# BreadShieldUno.net
KiCad netlist of a schematic drawn in EAGLE
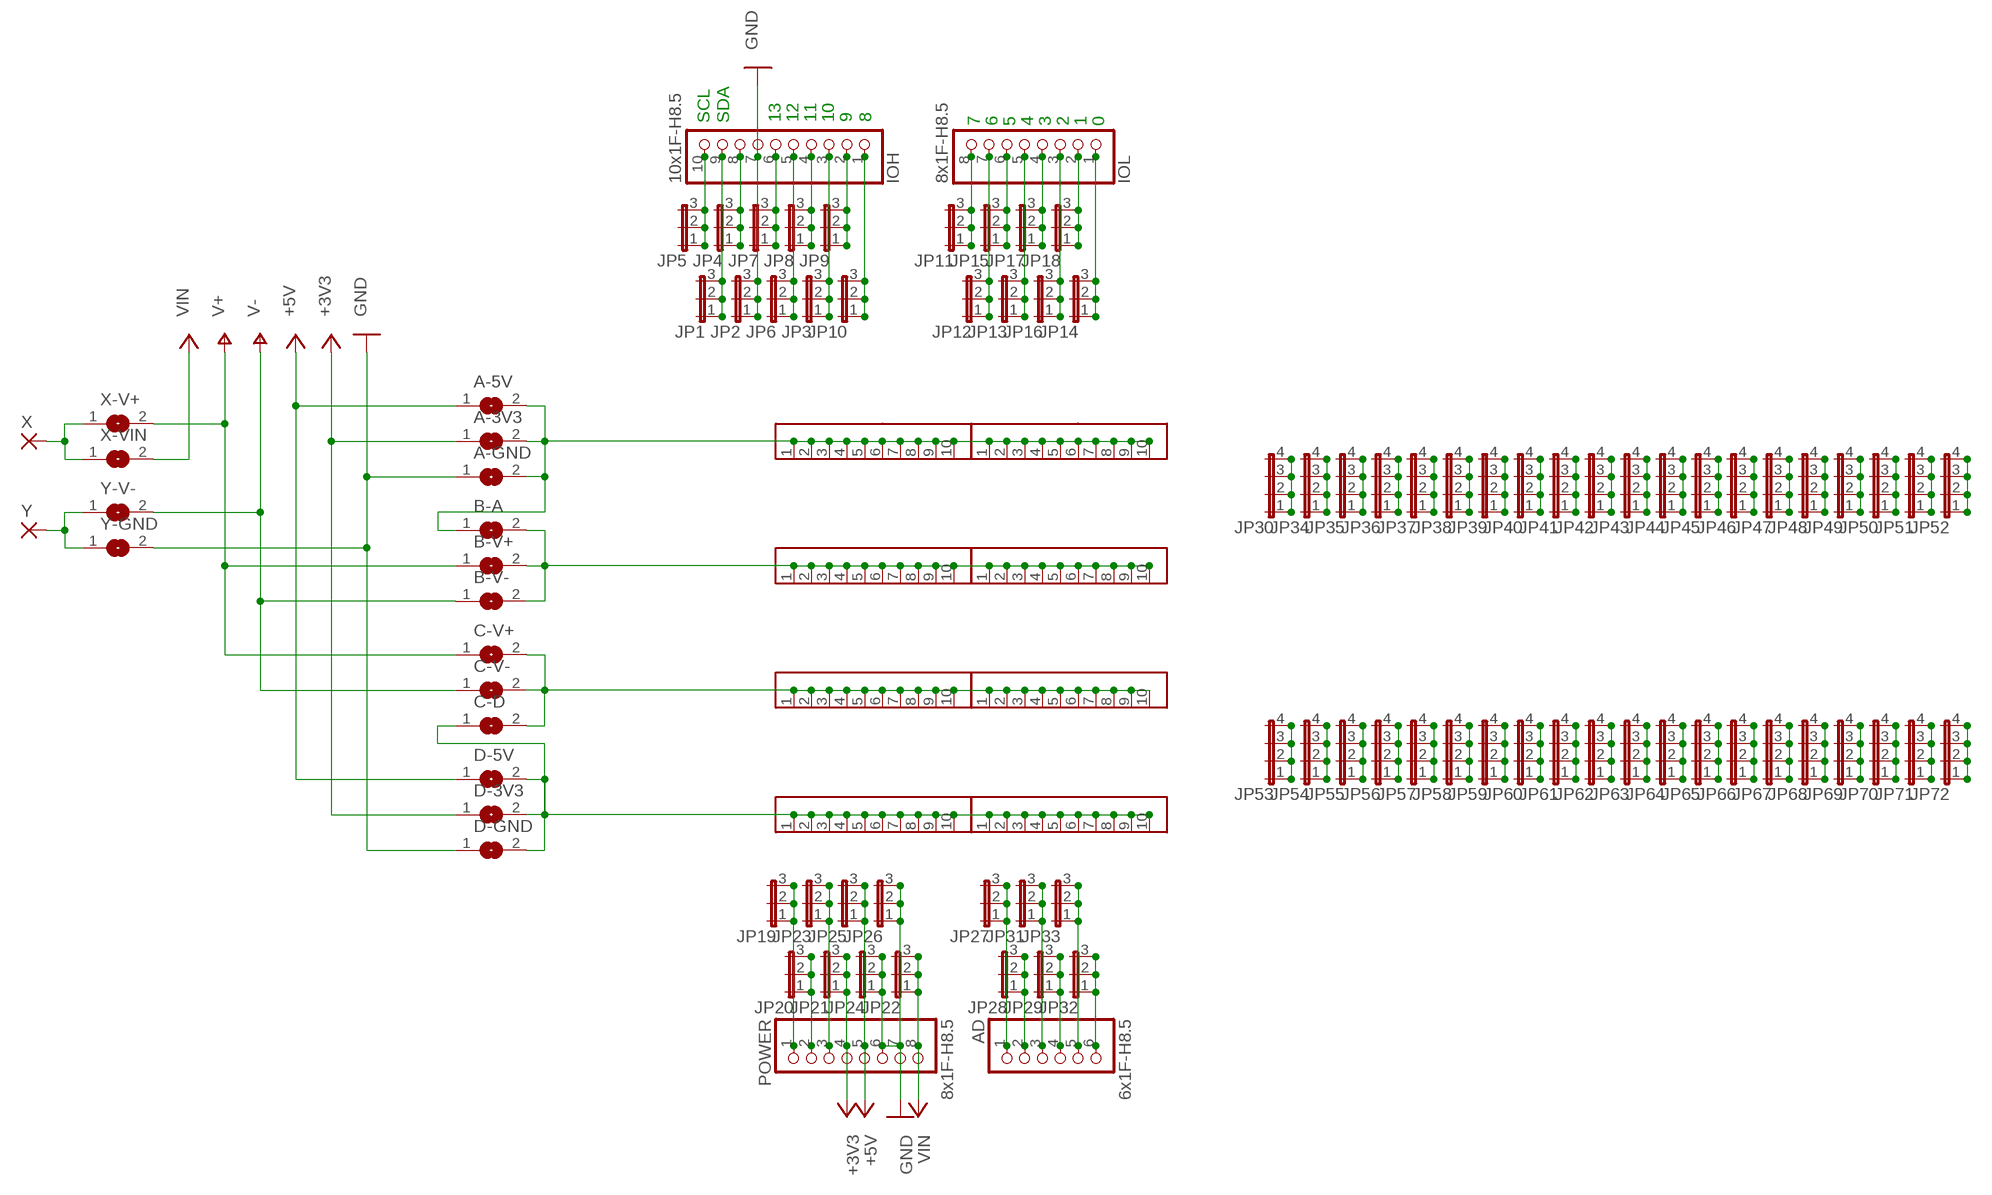
[diagram p0: schematic, sheet 1]

(export (version "E")
  (design (tool "Eeschema 10.0.6"))
  (components
    (comp (ref "A")
      (value "JP10B")
      (footprint "eagle-import:JP10-1")
      (libsource (lib "eagle-import") (part "JP10B"))
    )
    (comp (ref "A-3V3")
      (value "SJ")
      (footprint "eagle-import:SJ")
      (libsource (lib "eagle-import") (part "SJ"))
    )
    (comp (ref "A-5V")
      (value "SJ")
      (footprint "eagle-import:SJ")
      (libsource (lib "eagle-import") (part "SJ"))
    )
    (comp (ref "A-GND")
      (value "SJ")
      (footprint "eagle-import:SJ")
      (libsource (lib "eagle-import") (part "SJ"))
    )
    (comp (ref "A2")
      (value "JP10B")
      (footprint "eagle-import:JP10-1")
      (libsource (lib "eagle-import") (part "JP10B"))
    )
    (comp (ref "AD")
      (value "6x1F-H8.5")
      (footprint "eagle-import:1X06")
      (libsource (lib "eagle-import") (part "PINHD-1X6"))
    )
    (comp (ref "B")
      (value "JP10B")
      (footprint "eagle-import:JP10-1")
      (libsource (lib "eagle-import") (part "JP10B"))
    )
    (comp (ref "B-A") (value "SJ") (footprint "eagle-import:SJ") (libsource (lib "eagle-import") (part "SJ")))
    (comp (ref "B-V+")
      (value "SJ")
      (footprint "eagle-import:SJ")
      (libsource (lib "eagle-import") (part "SJ"))
    )
    (comp (ref "B-V-")
      (value "SJ")
      (footprint "eagle-import:SJ")
      (libsource (lib "eagle-import") (part "SJ"))
    )
    (comp (ref "B2")
      (value "JP10B")
      (footprint "eagle-import:JP10-1")
      (libsource (lib "eagle-import") (part "JP10B"))
    )
    (comp (ref "C")
      (value "JP10B")
      (footprint "eagle-import:JP10-1")
      (libsource (lib "eagle-import") (part "JP10B"))
    )
    (comp (ref "C-D") (value "SJ") (footprint "eagle-import:SJ") (libsource (lib "eagle-import") (part "SJ")))
    (comp (ref "C-V+")
      (value "SJ")
      (footprint "eagle-import:SJ")
      (libsource (lib "eagle-import") (part "SJ"))
    )
    (comp (ref "C-V-")
      (value "SJ")
      (footprint "eagle-import:SJ")
      (libsource (lib "eagle-import") (part "SJ"))
    )
    (comp (ref "C2")
      (value "JP10B")
      (footprint "eagle-import:JP10-1")
      (libsource (lib "eagle-import") (part "JP10B"))
    )
    (comp (ref "D")
      (value "JP10B")
      (footprint "eagle-import:JP10-1")
      (libsource (lib "eagle-import") (part "JP10B"))
    )
    (comp (ref "D-3V3")
      (value "SJ")
      (footprint "eagle-import:SJ")
      (libsource (lib "eagle-import") (part "SJ"))
    )
    (comp (ref "D-5V")
      (value "SJ")
      (footprint "eagle-import:SJ")
      (libsource (lib "eagle-import") (part "SJ"))
    )
    (comp (ref "D-GND")
      (value "SJ")
      (footprint "eagle-import:SJ")
      (libsource (lib "eagle-import") (part "SJ"))
    )
    (comp (ref "D2")
      (value "JP10B")
      (footprint "eagle-import:JP10-1")
      (libsource (lib "eagle-import") (part "JP10B"))
    )
    (comp (ref "IOH")
      (value "10x1F-H8.5")
      (footprint "eagle-import:1X10")
      (libsource (lib "eagle-import") (part "PINHD-1X10_ARD"))
    )
    (comp (ref "IOL")
      (value "8x1F-H8.5")
      (footprint "eagle-import:1X08")
      (libsource (lib "eagle-import") (part "PINHD-1X8"))
    )
    (comp (ref "JP1")
      (value "JP2E")
      (footprint "eagle-import:JP2")
      (libsource (lib "eagle-import") (part "JP2E"))
    )
    (comp (ref "JP2")
      (value "JP2E")
      (footprint "eagle-import:JP2")
      (libsource (lib "eagle-import") (part "JP2E"))
    )
    (comp (ref "JP3")
      (value "JP2E")
      (footprint "eagle-import:JP2")
      (libsource (lib "eagle-import") (part "JP2E"))
    )
    (comp (ref "JP4")
      (value "JP2E")
      (footprint "eagle-import:JP2")
      (libsource (lib "eagle-import") (part "JP2E"))
    )
    (comp (ref "JP5")
      (value "JP2E")
      (footprint "eagle-import:JP2")
      (libsource (lib "eagle-import") (part "JP2E"))
    )
    (comp (ref "JP6")
      (value "JP2E")
      (footprint "eagle-import:JP2")
      (libsource (lib "eagle-import") (part "JP2E"))
    )
    (comp (ref "JP7")
      (value "JP2E")
      (footprint "eagle-import:JP2")
      (libsource (lib "eagle-import") (part "JP2E"))
    )
    (comp (ref "JP8")
      (value "JP2E")
      (footprint "eagle-import:JP2")
      (libsource (lib "eagle-import") (part "JP2E"))
    )
    (comp (ref "JP9")
      (value "JP2E")
      (footprint "eagle-import:JP2")
      (libsource (lib "eagle-import") (part "JP2E"))
    )
    (comp (ref "JP10")
      (value "JP2E")
      (footprint "eagle-import:JP2")
      (libsource (lib "eagle-import") (part "JP2E"))
    )
    (comp (ref "JP11")
      (value "JP2E")
      (footprint "eagle-import:JP2")
      (libsource (lib "eagle-import") (part "JP2E"))
    )
    (comp (ref "JP12")
      (value "JP2E")
      (footprint "eagle-import:JP2")
      (libsource (lib "eagle-import") (part "JP2E"))
    )
    (comp (ref "JP13")
      (value "JP2E")
      (footprint "eagle-import:JP2")
      (libsource (lib "eagle-import") (part "JP2E"))
    )
    (comp (ref "JP14")
      (value "JP2E")
      (footprint "eagle-import:JP2")
      (libsource (lib "eagle-import") (part "JP2E"))
    )
    (comp (ref "JP15")
      (value "JP2E")
      (footprint "eagle-import:JP2")
      (libsource (lib "eagle-import") (part "JP2E"))
    )
    (comp (ref "JP16")
      (value "JP2E")
      (footprint "eagle-import:JP2")
      (libsource (lib "eagle-import") (part "JP2E"))
    )
    (comp (ref "JP17")
      (value "JP2E")
      (footprint "eagle-import:JP2")
      (libsource (lib "eagle-import") (part "JP2E"))
    )
    (comp (ref "JP18")
      (value "JP2E")
      (footprint "eagle-import:JP2")
      (libsource (lib "eagle-import") (part "JP2E"))
    )
    (comp (ref "JP19")
      (value "JP2E")
      (footprint "eagle-import:JP2")
      (libsource (lib "eagle-import") (part "JP2E"))
    )
    (comp (ref "JP20")
      (value "JP2E")
      (footprint "eagle-import:JP2")
      (libsource (lib "eagle-import") (part "JP2E"))
    )
    (comp (ref "JP21")
      (value "JP2E")
      (footprint "eagle-import:JP2")
      (libsource (lib "eagle-import") (part "JP2E"))
    )
    (comp (ref "JP22")
      (value "JP2E")
      (footprint "eagle-import:JP2")
      (libsource (lib "eagle-import") (part "JP2E"))
    )
    (comp (ref "JP23")
      (value "JP2E")
      (footprint "eagle-import:JP2")
      (libsource (lib "eagle-import") (part "JP2E"))
    )
    (comp (ref "JP24")
      (value "JP2E")
      (footprint "eagle-import:JP2")
      (libsource (lib "eagle-import") (part "JP2E"))
    )
    (comp (ref "JP25")
      (value "JP2E")
      (footprint "eagle-import:JP2")
      (libsource (lib "eagle-import") (part "JP2E"))
    )
    (comp (ref "JP26")
      (value "JP2E")
      (footprint "eagle-import:JP2")
      (libsource (lib "eagle-import") (part "JP2E"))
    )
    (comp (ref "JP27")
      (value "JP2E")
      (footprint "eagle-import:JP2")
      (libsource (lib "eagle-import") (part "JP2E"))
    )
    (comp (ref "JP28")
      (value "JP2E")
      (footprint "eagle-import:JP2")
      (libsource (lib "eagle-import") (part "JP2E"))
    )
    (comp (ref "JP29")
      (value "JP2E")
      (footprint "eagle-import:JP2")
      (libsource (lib "eagle-import") (part "JP2E"))
    )
    (comp (ref "JP30")
      (value "JP4E")
      (footprint "eagle-import:JP4")
      (libsource (lib "eagle-import") (part "JP4E"))
    )
    (comp (ref "JP31")
      (value "JP2E")
      (footprint "eagle-import:JP2")
      (libsource (lib "eagle-import") (part "JP2E"))
    )
    (comp (ref "JP32")
      (value "JP2E")
      (footprint "eagle-import:JP2")
      (libsource (lib "eagle-import") (part "JP2E"))
    )
    (comp (ref "JP33")
      (value "JP2E")
      (footprint "eagle-import:JP2")
      (libsource (lib "eagle-import") (part "JP2E"))
    )
    (comp (ref "JP34")
      (value "JP4E")
      (footprint "eagle-import:JP4")
      (libsource (lib "eagle-import") (part "JP4E"))
    )
    (comp (ref "JP35")
      (value "JP4E")
      (footprint "eagle-import:JP4")
      (libsource (lib "eagle-import") (part "JP4E"))
    )
    (comp (ref "JP36")
      (value "JP4E")
      (footprint "eagle-import:JP4")
      (libsource (lib "eagle-import") (part "JP4E"))
    )
    (comp (ref "JP37")
      (value "JP4E")
      (footprint "eagle-import:JP4")
      (libsource (lib "eagle-import") (part "JP4E"))
    )
    (comp (ref "JP38")
      (value "JP4E")
      (footprint "eagle-import:JP4")
      (libsource (lib "eagle-import") (part "JP4E"))
    )
    (comp (ref "JP39")
      (value "JP4E")
      (footprint "eagle-import:JP4")
      (libsource (lib "eagle-import") (part "JP4E"))
    )
    (comp (ref "JP40")
      (value "JP4E")
      (footprint "eagle-import:JP4")
      (libsource (lib "eagle-import") (part "JP4E"))
    )
    (comp (ref "JP41")
      (value "JP4E")
      (footprint "eagle-import:JP4")
      (libsource (lib "eagle-import") (part "JP4E"))
    )
    (comp (ref "JP42")
      (value "JP4E")
      (footprint "eagle-import:JP4")
      (libsource (lib "eagle-import") (part "JP4E"))
    )
    (comp (ref "JP43")
      (value "JP4E")
      (footprint "eagle-import:JP4")
      (libsource (lib "eagle-import") (part "JP4E"))
    )
    (comp (ref "JP44")
      (value "JP4E")
      (footprint "eagle-import:JP4")
      (libsource (lib "eagle-import") (part "JP4E"))
    )
    (comp (ref "JP45")
      (value "JP4E")
      (footprint "eagle-import:JP4")
      (libsource (lib "eagle-import") (part "JP4E"))
    )
    (comp (ref "JP46")
      (value "JP4E")
      (footprint "eagle-import:JP4")
      (libsource (lib "eagle-import") (part "JP4E"))
    )
    (comp (ref "JP47")
      (value "JP4E")
      (footprint "eagle-import:JP4")
      (libsource (lib "eagle-import") (part "JP4E"))
    )
    (comp (ref "JP48")
      (value "JP4E")
      (footprint "eagle-import:JP4")
      (libsource (lib "eagle-import") (part "JP4E"))
    )
    (comp (ref "JP49")
      (value "JP4E")
      (footprint "eagle-import:JP4")
      (libsource (lib "eagle-import") (part "JP4E"))
    )
    (comp (ref "JP50")
      (value "JP4E")
      (footprint "eagle-import:JP4")
      (libsource (lib "eagle-import") (part "JP4E"))
    )
    (comp (ref "JP51")
      (value "JP4E")
      (footprint "eagle-import:JP4")
      (libsource (lib "eagle-import") (part "JP4E"))
    )
    (comp (ref "JP52")
      (value "JP4E")
      (footprint "eagle-import:JP4")
      (libsource (lib "eagle-import") (part "JP4E"))
    )
    (comp (ref "JP53")
      (value "JP4E")
      (footprint "eagle-import:JP4")
      (libsource (lib "eagle-import") (part "JP4E"))
    )
    (comp (ref "JP54")
      (value "JP4E")
      (footprint "eagle-import:JP4")
      (libsource (lib "eagle-import") (part "JP4E"))
    )
    (comp (ref "JP55")
      (value "JP4E")
      (footprint "eagle-import:JP4")
      (libsource (lib "eagle-import") (part "JP4E"))
    )
    (comp (ref "JP56")
      (value "JP4E")
      (footprint "eagle-import:JP4")
      (libsource (lib "eagle-import") (part "JP4E"))
    )
    (comp (ref "JP57")
      (value "JP4E")
      (footprint "eagle-import:JP4")
      (libsource (lib "eagle-import") (part "JP4E"))
    )
    (comp (ref "JP58")
      (value "JP4E")
      (footprint "eagle-import:JP4")
      (libsource (lib "eagle-import") (part "JP4E"))
    )
    (comp (ref "JP59")
      (value "JP4E")
      (footprint "eagle-import:JP4")
      (libsource (lib "eagle-import") (part "JP4E"))
    )
    (comp (ref "JP60")
      (value "JP4E")
      (footprint "eagle-import:JP4")
      (libsource (lib "eagle-import") (part "JP4E"))
    )
    (comp (ref "JP61")
      (value "JP4E")
      (footprint "eagle-import:JP4")
      (libsource (lib "eagle-import") (part "JP4E"))
    )
    (comp (ref "JP62")
      (value "JP4E")
      (footprint "eagle-import:JP4")
      (libsource (lib "eagle-import") (part "JP4E"))
    )
    (comp (ref "JP63")
      (value "JP4E")
      (footprint "eagle-import:JP4")
      (libsource (lib "eagle-import") (part "JP4E"))
    )
    (comp (ref "JP64")
      (value "JP4E")
      (footprint "eagle-import:JP4")
      (libsource (lib "eagle-import") (part "JP4E"))
    )
    (comp (ref "JP65")
      (value "JP4E")
      (footprint "eagle-import:JP4")
      (libsource (lib "eagle-import") (part "JP4E"))
    )
    (comp (ref "JP66")
      (value "JP4E")
      (footprint "eagle-import:JP4")
      (libsource (lib "eagle-import") (part "JP4E"))
    )
    (comp (ref "JP67")
      (value "JP4E")
      (footprint "eagle-import:JP4")
      (libsource (lib "eagle-import") (part "JP4E"))
    )
    (comp (ref "JP68")
      (value "JP4E")
      (footprint "eagle-import:JP4")
      (libsource (lib "eagle-import") (part "JP4E"))
    )
    (comp (ref "JP69")
      (value "JP4E")
      (footprint "eagle-import:JP4")
      (libsource (lib "eagle-import") (part "JP4E"))
    )
    (comp (ref "JP70")
      (value "JP4E")
      (footprint "eagle-import:JP4")
      (libsource (lib "eagle-import") (part "JP4E"))
    )
    (comp (ref "JP71")
      (value "JP4E")
      (footprint "eagle-import:JP4")
      (libsource (lib "eagle-import") (part "JP4E"))
    )
    (comp (ref "JP72")
      (value "JP4E")
      (footprint "eagle-import:JP4")
      (libsource (lib "eagle-import") (part "JP4E"))
    )
    (comp (ref "POWER")
      (value "8x1F-H8.5")
      (footprint "eagle-import:1X08")
      (libsource (lib "eagle-import") (part "PINHD-1X8"))
    )
    (comp (ref "X")
      (value "3,81/1,4")
      (footprint "eagle-import:3,81_1,4")
      (libsource (lib "eagle-import") (part "3,81/1,4"))
    )
    (comp (ref "X-V+")
      (value "SJ")
      (footprint "eagle-import:SJ")
      (libsource (lib "eagle-import") (part "SJ"))
    )
    (comp (ref "X-VIN")
      (value "SJ")
      (footprint "eagle-import:SJ")
      (libsource (lib "eagle-import") (part "SJ"))
    )
    (comp (ref "Y")
      (value "3,81/1,4")
      (footprint "eagle-import:3,81_1,4")
      (libsource (lib "eagle-import") (part "3,81/1,4"))
    )
    (comp (ref "Y-GND")
      (value "SJ")
      (footprint "eagle-import:SJ")
      (libsource (lib "eagle-import") (part "SJ"))
    )
    (comp (ref "Y-V-")
      (value "SJ")
      (footprint "eagle-import:SJ")
      (libsource (lib "eagle-import") (part "SJ"))
    )
  )
  (nets
    (net (code "1") (name "+3V3") (class "Default")
      (node (ref "A-3V3") (pin "1") (pinfunction "1_1") (pintype "passive"))
      (node (ref "D-3V3") (pin "1") (pinfunction "1_1") (pintype "passive"))
      (node (ref "JP21") (pin "1") (pinfunction "1_1") (pintype "passive"))
      (node (ref "JP21") (pin "2") (pinfunction "2_2") (pintype "passive"))
      (node (ref "JP21") (pin "3") (pinfunction "3_3") (pintype "passive"))
      (node (ref "POWER") (pin "4") (pinfunction "4_4") (pintype "passive"))
    )
    (net (code "2") (name "+5V") (class "Default")
      (node (ref "A-5V") (pin "1") (pinfunction "1_1") (pintype "passive"))
      (node (ref "D-5V") (pin "1") (pinfunction "1_1") (pintype "passive"))
      (node (ref "JP25") (pin "1") (pinfunction "1_1") (pintype "passive"))
      (node (ref "JP25") (pin "2") (pinfunction "2_2") (pintype "passive"))
      (node (ref "JP25") (pin "3") (pinfunction "3_3") (pintype "passive"))
      (node (ref "POWER") (pin "5") (pinfunction "5_5") (pintype "passive"))
    )
    (net (code "3") (name "GND") (class "Default")
      (node (ref "A-GND") (pin "1") (pinfunction "1_1") (pintype "passive"))
      (node (ref "D-GND") (pin "1") (pinfunction "1_1") (pintype "passive"))
      (node (ref "IOH") (pin "7") (pinfunction "7_7") (pintype "passive"))
      (node (ref "JP2") (pin "1") (pinfunction "1_1") (pintype "passive"))
      (node (ref "JP2") (pin "2") (pinfunction "2_2") (pintype "passive"))
      (node (ref "JP2") (pin "3") (pinfunction "3_3") (pintype "passive"))
      (node (ref "JP24") (pin "1") (pinfunction "1_1") (pintype "passive"))
      (node (ref "JP24") (pin "2") (pinfunction "2_2") (pintype "passive"))
      (node (ref "JP24") (pin "3") (pinfunction "3_3") (pintype "passive"))
      (node (ref "JP26") (pin "1") (pinfunction "1_1") (pintype "passive"))
      (node (ref "JP26") (pin "2") (pinfunction "2_2") (pintype "passive"))
      (node (ref "JP26") (pin "3") (pinfunction "3_3") (pintype "passive"))
      (node (ref "POWER") (pin "6") (pinfunction "6_6") (pintype "passive"))
      (node (ref "POWER") (pin "7") (pinfunction "7_7") (pintype "passive"))
      (node (ref "Y-GND") (pin "2") (pinfunction "2_2") (pintype "passive"))
    )
    (net (code "4") (name "Net-(A-3V3-Pad2)") (class "Default")
      (node (ref "A") (pin "1") (pinfunction "1_1") (pintype "bidirectional"))
      (node (ref "A") (pin "10") (pinfunction "10_10") (pintype "bidirectional"))
      (node (ref "A") (pin "2") (pinfunction "2_2") (pintype "bidirectional"))
      (node (ref "A") (pin "3") (pinfunction "3_3") (pintype "bidirectional"))
      (node (ref "A") (pin "4") (pinfunction "4_4") (pintype "bidirectional"))
      (node (ref "A") (pin "5") (pinfunction "5_5") (pintype "bidirectional"))
      (node (ref "A") (pin "6") (pinfunction "6_6") (pintype "bidirectional"))
      (node (ref "A") (pin "7") (pinfunction "7_7") (pintype "bidirectional"))
      (node (ref "A") (pin "8") (pinfunction "8_8") (pintype "bidirectional"))
      (node (ref "A") (pin "9") (pinfunction "9_9") (pintype "bidirectional"))
      (node (ref "A-3V3") (pin "2") (pinfunction "2_2") (pintype "passive"))
      (node (ref "A-5V") (pin "2") (pinfunction "2_2") (pintype "passive"))
      (node (ref "A-GND") (pin "2") (pinfunction "2_2") (pintype "passive"))
      (node (ref "A2") (pin "1") (pinfunction "1_1") (pintype "bidirectional"))
      (node (ref "A2") (pin "10") (pinfunction "10_10") (pintype "bidirectional"))
      (node (ref "A2") (pin "2") (pinfunction "2_2") (pintype "bidirectional"))
      (node (ref "A2") (pin "3") (pinfunction "3_3") (pintype "bidirectional"))
      (node (ref "A2") (pin "4") (pinfunction "4_4") (pintype "bidirectional"))
      (node (ref "A2") (pin "5") (pinfunction "5_5") (pintype "bidirectional"))
      (node (ref "A2") (pin "6") (pinfunction "6_6") (pintype "bidirectional"))
      (node (ref "A2") (pin "7") (pinfunction "7_7") (pintype "bidirectional"))
      (node (ref "A2") (pin "8") (pinfunction "8_8") (pintype "bidirectional"))
      (node (ref "A2") (pin "9") (pinfunction "9_9") (pintype "bidirectional"))
      (node (ref "B-A") (pin "1") (pinfunction "1_1") (pintype "passive"))
    )
    (net (code "5") (name "Net-(AD-Pad1)") (class "Default")
      (node (ref "AD") (pin "1") (pinfunction "1_1") (pintype "passive"))
      (node (ref "JP27") (pin "1") (pinfunction "1_1") (pintype "passive"))
      (node (ref "JP27") (pin "2") (pinfunction "2_2") (pintype "passive"))
      (node (ref "JP27") (pin "3") (pinfunction "3_3") (pintype "passive"))
    )
    (net (code "6") (name "Net-(AD-Pad2)") (class "Default")
      (node (ref "AD") (pin "2") (pinfunction "2_2") (pintype "passive"))
      (node (ref "JP28") (pin "1") (pinfunction "1_1") (pintype "passive"))
      (node (ref "JP28") (pin "2") (pinfunction "2_2") (pintype "passive"))
      (node (ref "JP28") (pin "3") (pinfunction "3_3") (pintype "passive"))
    )
    (net (code "7") (name "Net-(AD-Pad3)") (class "Default")
      (node (ref "AD") (pin "3") (pinfunction "3_3") (pintype "passive"))
      (node (ref "JP31") (pin "1") (pinfunction "1_1") (pintype "passive"))
      (node (ref "JP31") (pin "2") (pinfunction "2_2") (pintype "passive"))
      (node (ref "JP31") (pin "3") (pinfunction "3_3") (pintype "passive"))
    )
    (net (code "8") (name "Net-(AD-Pad4)") (class "Default")
      (node (ref "AD") (pin "4") (pinfunction "4_4") (pintype "passive"))
      (node (ref "JP29") (pin "1") (pinfunction "1_1") (pintype "passive"))
      (node (ref "JP29") (pin "2") (pinfunction "2_2") (pintype "passive"))
      (node (ref "JP29") (pin "3") (pinfunction "3_3") (pintype "passive"))
    )
    (net (code "9") (name "Net-(AD-Pad5)") (class "Default")
      (node (ref "AD") (pin "5") (pinfunction "5_5") (pintype "passive"))
      (node (ref "JP33") (pin "1") (pinfunction "1_1") (pintype "passive"))
      (node (ref "JP33") (pin "2") (pinfunction "2_2") (pintype "passive"))
      (node (ref "JP33") (pin "3") (pinfunction "3_3") (pintype "passive"))
    )
    (net (code "10") (name "Net-(AD-Pad6)") (class "Default")
      (node (ref "AD") (pin "6") (pinfunction "6_6") (pintype "passive"))
      (node (ref "JP32") (pin "1") (pinfunction "1_1") (pintype "passive"))
      (node (ref "JP32") (pin "2") (pinfunction "2_2") (pintype "passive"))
      (node (ref "JP32") (pin "3") (pinfunction "3_3") (pintype "passive"))
    )
    (net (code "11") (name "Net-(B-A-Pad2)") (class "Default")
      (node (ref "B") (pin "1") (pinfunction "1_1") (pintype "bidirectional"))
      (node (ref "B") (pin "10") (pinfunction "10_10") (pintype "bidirectional"))
      (node (ref "B") (pin "2") (pinfunction "2_2") (pintype "bidirectional"))
      (node (ref "B") (pin "3") (pinfunction "3_3") (pintype "bidirectional"))
      (node (ref "B") (pin "4") (pinfunction "4_4") (pintype "bidirectional"))
      (node (ref "B") (pin "5") (pinfunction "5_5") (pintype "bidirectional"))
      (node (ref "B") (pin "6") (pinfunction "6_6") (pintype "bidirectional"))
      (node (ref "B") (pin "7") (pinfunction "7_7") (pintype "bidirectional"))
      (node (ref "B") (pin "8") (pinfunction "8_8") (pintype "bidirectional"))
      (node (ref "B") (pin "9") (pinfunction "9_9") (pintype "bidirectional"))
      (node (ref "B-A") (pin "2") (pinfunction "2_2") (pintype "passive"))
      (node (ref "B-V+") (pin "2") (pinfunction "2_2") (pintype "passive"))
      (node (ref "B-V-") (pin "2") (pinfunction "2_2") (pintype "passive"))
      (node (ref "B2") (pin "1") (pinfunction "1_1") (pintype "bidirectional"))
      (node (ref "B2") (pin "10") (pinfunction "10_10") (pintype "bidirectional"))
      (node (ref "B2") (pin "2") (pinfunction "2_2") (pintype "bidirectional"))
      (node (ref "B2") (pin "3") (pinfunction "3_3") (pintype "bidirectional"))
      (node (ref "B2") (pin "4") (pinfunction "4_4") (pintype "bidirectional"))
      (node (ref "B2") (pin "5") (pinfunction "5_5") (pintype "bidirectional"))
      (node (ref "B2") (pin "6") (pinfunction "6_6") (pintype "bidirectional"))
      (node (ref "B2") (pin "7") (pinfunction "7_7") (pintype "bidirectional"))
      (node (ref "B2") (pin "8") (pinfunction "8_8") (pintype "bidirectional"))
      (node (ref "B2") (pin "9") (pinfunction "9_9") (pintype "bidirectional"))
    )
    (net (code "12") (name "Net-(C-D-Pad1)") (class "Default")
      (node (ref "C-D") (pin "1") (pinfunction "1_1") (pintype "passive"))
      (node (ref "D") (pin "1") (pinfunction "1_1") (pintype "bidirectional"))
      (node (ref "D") (pin "10") (pinfunction "10_10") (pintype "bidirectional"))
      (node (ref "D") (pin "2") (pinfunction "2_2") (pintype "bidirectional"))
      (node (ref "D") (pin "3") (pinfunction "3_3") (pintype "bidirectional"))
      (node (ref "D") (pin "4") (pinfunction "4_4") (pintype "bidirectional"))
      (node (ref "D") (pin "5") (pinfunction "5_5") (pintype "bidirectional"))
      (node (ref "D") (pin "6") (pinfunction "6_6") (pintype "bidirectional"))
      (node (ref "D") (pin "7") (pinfunction "7_7") (pintype "bidirectional"))
      (node (ref "D") (pin "8") (pinfunction "8_8") (pintype "bidirectional"))
      (node (ref "D") (pin "9") (pinfunction "9_9") (pintype "bidirectional"))
      (node (ref "D-3V3") (pin "2") (pinfunction "2_2") (pintype "passive"))
      (node (ref "D-5V") (pin "2") (pinfunction "2_2") (pintype "passive"))
      (node (ref "D-GND") (pin "2") (pinfunction "2_2") (pintype "passive"))
      (node (ref "D2") (pin "1") (pinfunction "1_1") (pintype "bidirectional"))
      (node (ref "D2") (pin "10") (pinfunction "10_10") (pintype "bidirectional"))
      (node (ref "D2") (pin "2") (pinfunction "2_2") (pintype "bidirectional"))
      (node (ref "D2") (pin "3") (pinfunction "3_3") (pintype "bidirectional"))
      (node (ref "D2") (pin "4") (pinfunction "4_4") (pintype "bidirectional"))
      (node (ref "D2") (pin "5") (pinfunction "5_5") (pintype "bidirectional"))
      (node (ref "D2") (pin "6") (pinfunction "6_6") (pintype "bidirectional"))
      (node (ref "D2") (pin "7") (pinfunction "7_7") (pintype "bidirectional"))
      (node (ref "D2") (pin "8") (pinfunction "8_8") (pintype "bidirectional"))
      (node (ref "D2") (pin "9") (pinfunction "9_9") (pintype "bidirectional"))
    )
    (net (code "13") (name "Net-(C-D-Pad2)") (class "Default")
      (node (ref "C") (pin "1") (pinfunction "1_1") (pintype "bidirectional"))
      (node (ref "C") (pin "10") (pinfunction "10_10") (pintype "bidirectional"))
      (node (ref "C") (pin "2") (pinfunction "2_2") (pintype "bidirectional"))
      (node (ref "C") (pin "3") (pinfunction "3_3") (pintype "bidirectional"))
      (node (ref "C") (pin "4") (pinfunction "4_4") (pintype "bidirectional"))
      (node (ref "C") (pin "5") (pinfunction "5_5") (pintype "bidirectional"))
      (node (ref "C") (pin "6") (pinfunction "6_6") (pintype "bidirectional"))
      (node (ref "C") (pin "7") (pinfunction "7_7") (pintype "bidirectional"))
      (node (ref "C") (pin "8") (pinfunction "8_8") (pintype "bidirectional"))
      (node (ref "C") (pin "9") (pinfunction "9_9") (pintype "bidirectional"))
      (node (ref "C-D") (pin "2") (pinfunction "2_2") (pintype "passive"))
      (node (ref "C-V+") (pin "2") (pinfunction "2_2") (pintype "passive"))
      (node (ref "C-V-") (pin "2") (pinfunction "2_2") (pintype "passive"))
      (node (ref "C2") (pin "1") (pinfunction "1_1") (pintype "bidirectional"))
      (node (ref "C2") (pin "10") (pinfunction "10_10") (pintype "bidirectional"))
      (node (ref "C2") (pin "2") (pinfunction "2_2") (pintype "bidirectional"))
      (node (ref "C2") (pin "3") (pinfunction "3_3") (pintype "bidirectional"))
      (node (ref "C2") (pin "4") (pinfunction "4_4") (pintype "bidirectional"))
      (node (ref "C2") (pin "5") (pinfunction "5_5") (pintype "bidirectional"))
      (node (ref "C2") (pin "6") (pinfunction "6_6") (pintype "bidirectional"))
      (node (ref "C2") (pin "7") (pinfunction "7_7") (pintype "bidirectional"))
      (node (ref "C2") (pin "8") (pinfunction "8_8") (pintype "bidirectional"))
      (node (ref "C2") (pin "9") (pinfunction "9_9") (pintype "bidirectional"))
    )
    (net (code "14") (name "Net-(IOH-Pad1)") (class "Default")
      (node (ref "IOH") (pin "1") (pinfunction "1_1") (pintype "passive"))
      (node (ref "JP10") (pin "1") (pinfunction "1_1") (pintype "passive"))
      (node (ref "JP10") (pin "2") (pinfunction "2_2") (pintype "passive"))
      (node (ref "JP10") (pin "3") (pinfunction "3_3") (pintype "passive"))
    )
    (net (code "15") (name "Net-(IOH-Pad2)") (class "Default")
      (node (ref "IOH") (pin "2") (pinfunction "2_2") (pintype "passive"))
      (node (ref "JP9") (pin "1") (pinfunction "1_1") (pintype "passive"))
      (node (ref "JP9") (pin "2") (pinfunction "2_2") (pintype "passive"))
      (node (ref "JP9") (pin "3") (pinfunction "3_3") (pintype "passive"))
    )
    (net (code "16") (name "Net-(IOH-Pad3)") (class "Default")
      (node (ref "IOH") (pin "3") (pinfunction "3_3") (pintype "passive"))
      (node (ref "JP3") (pin "1") (pinfunction "1_1") (pintype "passive"))
      (node (ref "JP3") (pin "2") (pinfunction "2_2") (pintype "passive"))
      (node (ref "JP3") (pin "3") (pinfunction "3_3") (pintype "passive"))
    )
    (net (code "17") (name "Net-(IOH-Pad4)") (class "Default")
      (node (ref "IOH") (pin "4") (pinfunction "4_4") (pintype "passive"))
      (node (ref "JP8") (pin "1") (pinfunction "1_1") (pintype "passive"))
      (node (ref "JP8") (pin "2") (pinfunction "2_2") (pintype "passive"))
      (node (ref "JP8") (pin "3") (pinfunction "3_3") (pintype "passive"))
    )
    (net (code "18") (name "Net-(IOH-Pad5)") (class "Default")
      (node (ref "IOH") (pin "5") (pinfunction "5_5") (pintype "passive"))
      (node (ref "JP6") (pin "1") (pinfunction "1_1") (pintype "passive"))
      (node (ref "JP6") (pin "2") (pinfunction "2_2") (pintype "passive"))
      (node (ref "JP6") (pin "3") (pinfunction "3_3") (pintype "passive"))
    )
    (net (code "19") (name "Net-(IOH-Pad6)") (class "Default")
      (node (ref "IOH") (pin "6") (pinfunction "6_6") (pintype "passive"))
      (node (ref "JP7") (pin "1") (pinfunction "1_1") (pintype "passive"))
      (node (ref "JP7") (pin "2") (pinfunction "2_2") (pintype "passive"))
      (node (ref "JP7") (pin "3") (pinfunction "3_3") (pintype "passive"))
    )
    (net (code "20") (name "Net-(IOH-Pad8)") (class "Default")
      (node (ref "IOH") (pin "8") (pinfunction "8_8") (pintype "passive"))
      (node (ref "JP4") (pin "1") (pinfunction "1_1") (pintype "passive"))
      (node (ref "JP4") (pin "2") (pinfunction "2_2") (pintype "passive"))
      (node (ref "JP4") (pin "3") (pinfunction "3_3") (pintype "passive"))
    )
    (net (code "21") (name "Net-(IOH-Pad9)") (class "Default")
      (node (ref "IOH") (pin "9") (pinfunction "9_9") (pintype "passive"))
      (node (ref "JP1") (pin "1") (pinfunction "1_1") (pintype "passive"))
      (node (ref "JP1") (pin "2") (pinfunction "2_2") (pintype "passive"))
      (node (ref "JP1") (pin "3") (pinfunction "3_3") (pintype "passive"))
    )
    (net (code "22") (name "Net-(IOH-Pad10)") (class "Default")
      (node (ref "IOH") (pin "10") (pinfunction "10_10") (pintype "passive"))
      (node (ref "JP5") (pin "1") (pinfunction "1_1") (pintype "passive"))
      (node (ref "JP5") (pin "2") (pinfunction "2_2") (pintype "passive"))
      (node (ref "JP5") (pin "3") (pinfunction "3_3") (pintype "passive"))
    )
    (net (code "23") (name "Net-(IOL-Pad1)") (class "Default")
      (node (ref "IOL") (pin "1") (pinfunction "1_1") (pintype "passive"))
      (node (ref "JP14") (pin "1") (pinfunction "1_1") (pintype "passive"))
      (node (ref "JP14") (pin "2") (pinfunction "2_2") (pintype "passive"))
      (node (ref "JP14") (pin "3") (pinfunction "3_3") (pintype "passive"))
    )
    (net (code "24") (name "Net-(IOL-Pad2)") (class "Default")
      (node (ref "IOL") (pin "2") (pinfunction "2_2") (pintype "passive"))
      (node (ref "JP18") (pin "1") (pinfunction "1_1") (pintype "passive"))
      (node (ref "JP18") (pin "2") (pinfunction "2_2") (pintype "passive"))
      (node (ref "JP18") (pin "3") (pinfunction "3_3") (pintype "passive"))
    )
    (net (code "25") (name "Net-(IOL-Pad3)") (class "Default")
      (node (ref "IOL") (pin "3") (pinfunction "3_3") (pintype "passive"))
      (node (ref "JP16") (pin "1") (pinfunction "1_1") (pintype "passive"))
      (node (ref "JP16") (pin "2") (pinfunction "2_2") (pintype "passive"))
      (node (ref "JP16") (pin "3") (pinfunction "3_3") (pintype "passive"))
    )
    (net (code "26") (name "Net-(IOL-Pad4)") (class "Default")
      (node (ref "IOL") (pin "4") (pinfunction "4_4") (pintype "passive"))
      (node (ref "JP17") (pin "1") (pinfunction "1_1") (pintype "passive"))
      (node (ref "JP17") (pin "2") (pinfunction "2_2") (pintype "passive"))
      (node (ref "JP17") (pin "3") (pinfunction "3_3") (pintype "passive"))
    )
    (net (code "27") (name "Net-(IOL-Pad5)") (class "Default")
      (node (ref "IOL") (pin "5") (pinfunction "5_5") (pintype "passive"))
      (node (ref "JP13") (pin "1") (pinfunction "1_1") (pintype "passive"))
      (node (ref "JP13") (pin "2") (pinfunction "2_2") (pintype "passive"))
      (node (ref "JP13") (pin "3") (pinfunction "3_3") (pintype "passive"))
    )
    (net (code "28") (name "Net-(IOL-Pad6)") (class "Default")
      (node (ref "IOL") (pin "6") (pinfunction "6_6") (pintype "passive"))
      (node (ref "JP15") (pin "1") (pinfunction "1_1") (pintype "passive"))
      (node (ref "JP15") (pin "2") (pinfunction "2_2") (pintype "passive"))
      (node (ref "JP15") (pin "3") (pinfunction "3_3") (pintype "passive"))
    )
    (net (code "29") (name "Net-(IOL-Pad7)") (class "Default")
      (node (ref "IOL") (pin "7") (pinfunction "7_7") (pintype "passive"))
      (node (ref "JP12") (pin "1") (pinfunction "1_1") (pintype "passive"))
      (node (ref "JP12") (pin "2") (pinfunction "2_2") (pintype "passive"))
      (node (ref "JP12") (pin "3") (pinfunction "3_3") (pintype "passive"))
    )
    (net (code "30") (name "Net-(IOL-Pad8)") (class "Default")
      (node (ref "IOL") (pin "8") (pinfunction "8_8") (pintype "passive"))
      (node (ref "JP11") (pin "1") (pinfunction "1_1") (pintype "passive"))
      (node (ref "JP11") (pin "2") (pinfunction "2_2") (pintype "passive"))
      (node (ref "JP11") (pin "3") (pinfunction "3_3") (pintype "passive"))
    )
    (net (code "31") (name "Net-(JP19-Pad1)") (class "Default")
      (node (ref "JP19") (pin "1") (pinfunction "1_1") (pintype "passive"))
      (node (ref "JP19") (pin "2") (pinfunction "2_2") (pintype "passive"))
      (node (ref "JP19") (pin "3") (pinfunction "3_3") (pintype "passive"))
      (node (ref "POWER") (pin "1") (pinfunction "1_1") (pintype "passive"))
    )
    (net (code "32") (name "Net-(JP20-Pad1)") (class "Default")
      (node (ref "JP20") (pin "1") (pinfunction "1_1") (pintype "passive"))
      (node (ref "JP20") (pin "2") (pinfunction "2_2") (pintype "passive"))
      (node (ref "JP20") (pin "3") (pinfunction "3_3") (pintype "passive"))
      (node (ref "POWER") (pin "2") (pinfunction "2_2") (pintype "passive"))
    )
    (net (code "33") (name "Net-(JP23-Pad1)") (class "Default")
      (node (ref "JP23") (pin "1") (pinfunction "1_1") (pintype "passive"))
      (node (ref "JP23") (pin "2") (pinfunction "2_2") (pintype "passive"))
      (node (ref "JP23") (pin "3") (pinfunction "3_3") (pintype "passive"))
      (node (ref "POWER") (pin "3") (pinfunction "3_3") (pintype "passive"))
    )
    (net (code "34") (name "Net-(JP30-Pad1)") (class "Default")
      (node (ref "JP30") (pin "1") (pinfunction "1_1") (pintype "passive"))
      (node (ref "JP30") (pin "2") (pinfunction "2_2") (pintype "passive"))
      (node (ref "JP30") (pin "3") (pinfunction "3_3") (pintype "passive"))
      (node (ref "JP30") (pin "4") (pinfunction "4_4") (pintype "passive"))
    )
    (net (code "35") (name "Net-(JP34-Pad1)") (class "Default")
      (node (ref "JP34") (pin "1") (pinfunction "1_1") (pintype "passive"))
      (node (ref "JP34") (pin "2") (pinfunction "2_2") (pintype "passive"))
      (node (ref "JP34") (pin "3") (pinfunction "3_3") (pintype "passive"))
      (node (ref "JP34") (pin "4") (pinfunction "4_4") (pintype "passive"))
    )
    (net (code "36") (name "Net-(JP35-Pad1)") (class "Default")
      (node (ref "JP35") (pin "1") (pinfunction "1_1") (pintype "passive"))
      (node (ref "JP35") (pin "2") (pinfunction "2_2") (pintype "passive"))
      (node (ref "JP35") (pin "3") (pinfunction "3_3") (pintype "passive"))
      (node (ref "JP35") (pin "4") (pinfunction "4_4") (pintype "passive"))
    )
    (net (code "37") (name "Net-(JP36-Pad1)") (class "Default")
      (node (ref "JP36") (pin "1") (pinfunction "1_1") (pintype "passive"))
      (node (ref "JP36") (pin "2") (pinfunction "2_2") (pintype "passive"))
      (node (ref "JP36") (pin "3") (pinfunction "3_3") (pintype "passive"))
      (node (ref "JP36") (pin "4") (pinfunction "4_4") (pintype "passive"))
    )
    (net (code "38") (name "Net-(JP37-Pad1)") (class "Default")
      (node (ref "JP37") (pin "1") (pinfunction "1_1") (pintype "passive"))
      (node (ref "JP37") (pin "2") (pinfunction "2_2") (pintype "passive"))
      (node (ref "JP37") (pin "3") (pinfunction "3_3") (pintype "passive"))
      (node (ref "JP37") (pin "4") (pinfunction "4_4") (pintype "passive"))
    )
    (net (code "39") (name "Net-(JP38-Pad1)") (class "Default")
      (node (ref "JP38") (pin "1") (pinfunction "1_1") (pintype "passive"))
      (node (ref "JP38") (pin "2") (pinfunction "2_2") (pintype "passive"))
      (node (ref "JP38") (pin "3") (pinfunction "3_3") (pintype "passive"))
      (node (ref "JP38") (pin "4") (pinfunction "4_4") (pintype "passive"))
    )
    (net (code "40") (name "Net-(JP39-Pad1)") (class "Default")
      (node (ref "JP39") (pin "1") (pinfunction "1_1") (pintype "passive"))
      (node (ref "JP39") (pin "2") (pinfunction "2_2") (pintype "passive"))
      (node (ref "JP39") (pin "3") (pinfunction "3_3") (pintype "passive"))
      (node (ref "JP39") (pin "4") (pinfunction "4_4") (pintype "passive"))
    )
    (net (code "41") (name "Net-(JP40-Pad1)") (class "Default")
      (node (ref "JP40") (pin "1") (pinfunction "1_1") (pintype "passive"))
      (node (ref "JP40") (pin "2") (pinfunction "2_2") (pintype "passive"))
      (node (ref "JP40") (pin "3") (pinfunction "3_3") (pintype "passive"))
      (node (ref "JP40") (pin "4") (pinfunction "4_4") (pintype "passive"))
    )
    (net (code "42") (name "Net-(JP41-Pad1)") (class "Default")
      (node (ref "JP41") (pin "1") (pinfunction "1_1") (pintype "passive"))
      (node (ref "JP41") (pin "2") (pinfunction "2_2") (pintype "passive"))
      (node (ref "JP41") (pin "3") (pinfunction "3_3") (pintype "passive"))
      (node (ref "JP41") (pin "4") (pinfunction "4_4") (pintype "passive"))
    )
    (net (code "43") (name "Net-(JP42-Pad1)") (class "Default")
      (node (ref "JP42") (pin "1") (pinfunction "1_1") (pintype "passive"))
      (node (ref "JP42") (pin "2") (pinfunction "2_2") (pintype "passive"))
      (node (ref "JP42") (pin "3") (pinfunction "3_3") (pintype "passive"))
      (node (ref "JP42") (pin "4") (pinfunction "4_4") (pintype "passive"))
    )
    (net (code "44") (name "Net-(JP43-Pad1)") (class "Default")
      (node (ref "JP43") (pin "1") (pinfunction "1_1") (pintype "passive"))
      (node (ref "JP43") (pin "2") (pinfunction "2_2") (pintype "passive"))
      (node (ref "JP43") (pin "3") (pinfunction "3_3") (pintype "passive"))
      (node (ref "JP43") (pin "4") (pinfunction "4_4") (pintype "passive"))
    )
    (net (code "45") (name "Net-(JP44-Pad1)") (class "Default")
      (node (ref "JP44") (pin "1") (pinfunction "1_1") (pintype "passive"))
      (node (ref "JP44") (pin "2") (pinfunction "2_2") (pintype "passive"))
      (node (ref "JP44") (pin "3") (pinfunction "3_3") (pintype "passive"))
      (node (ref "JP44") (pin "4") (pinfunction "4_4") (pintype "passive"))
    )
    (net (code "46") (name "Net-(JP45-Pad1)") (class "Default")
      (node (ref "JP45") (pin "1") (pinfunction "1_1") (pintype "passive"))
      (node (ref "JP45") (pin "2") (pinfunction "2_2") (pintype "passive"))
      (node (ref "JP45") (pin "3") (pinfunction "3_3") (pintype "passive"))
      (node (ref "JP45") (pin "4") (pinfunction "4_4") (pintype "passive"))
    )
    (net (code "47") (name "Net-(JP46-Pad1)") (class "Default")
      (node (ref "JP46") (pin "1") (pinfunction "1_1") (pintype "passive"))
      (node (ref "JP46") (pin "2") (pinfunction "2_2") (pintype "passive"))
      (node (ref "JP46") (pin "3") (pinfunction "3_3") (pintype "passive"))
      (node (ref "JP46") (pin "4") (pinfunction "4_4") (pintype "passive"))
    )
    (net (code "48") (name "Net-(JP47-Pad1)") (class "Default")
      (node (ref "JP47") (pin "1") (pinfunction "1_1") (pintype "passive"))
      (node (ref "JP47") (pin "2") (pinfunction "2_2") (pintype "passive"))
      (node (ref "JP47") (pin "3") (pinfunction "3_3") (pintype "passive"))
      (node (ref "JP47") (pin "4") (pinfunction "4_4") (pintype "passive"))
    )
    (net (code "49") (name "Net-(JP48-Pad1)") (class "Default")
      (node (ref "JP48") (pin "1") (pinfunction "1_1") (pintype "passive"))
      (node (ref "JP48") (pin "2") (pinfunction "2_2") (pintype "passive"))
      (node (ref "JP48") (pin "3") (pinfunction "3_3") (pintype "passive"))
      (node (ref "JP48") (pin "4") (pinfunction "4_4") (pintype "passive"))
    )
    (net (code "50") (name "Net-(JP49-Pad1)") (class "Default")
      (node (ref "JP49") (pin "1") (pinfunction "1_1") (pintype "passive"))
      (node (ref "JP49") (pin "2") (pinfunction "2_2") (pintype "passive"))
      (node (ref "JP49") (pin "3") (pinfunction "3_3") (pintype "passive"))
      (node (ref "JP49") (pin "4") (pinfunction "4_4") (pintype "passive"))
    )
    (net (code "51") (name "Net-(JP50-Pad1)") (class "Default")
      (node (ref "JP50") (pin "1") (pinfunction "1_1") (pintype "passive"))
      (node (ref "JP50") (pin "2") (pinfunction "2_2") (pintype "passive"))
      (node (ref "JP50") (pin "3") (pinfunction "3_3") (pintype "passive"))
      (node (ref "JP50") (pin "4") (pinfunction "4_4") (pintype "passive"))
    )
    (net (code "52") (name "Net-(JP51-Pad1)") (class "Default")
      (node (ref "JP51") (pin "1") (pinfunction "1_1") (pintype "passive"))
      (node (ref "JP51") (pin "2") (pinfunction "2_2") (pintype "passive"))
      (node (ref "JP51") (pin "3") (pinfunction "3_3") (pintype "passive"))
      (node (ref "JP51") (pin "4") (pinfunction "4_4") (pintype "passive"))
    )
    (net (code "53") (name "Net-(JP52-Pad1)") (class "Default")
      (node (ref "JP52") (pin "1") (pinfunction "1_1") (pintype "passive"))
      (node (ref "JP52") (pin "2") (pinfunction "2_2") (pintype "passive"))
      (node (ref "JP52") (pin "3") (pinfunction "3_3") (pintype "passive"))
      (node (ref "JP52") (pin "4") (pinfunction "4_4") (pintype "passive"))
    )
    (net (code "54") (name "Net-(JP53-Pad1)") (class "Default")
      (node (ref "JP53") (pin "1") (pinfunction "1_1") (pintype "passive"))
      (node (ref "JP53") (pin "2") (pinfunction "2_2") (pintype "passive"))
      (node (ref "JP53") (pin "3") (pinfunction "3_3") (pintype "passive"))
      (node (ref "JP53") (pin "4") (pinfunction "4_4") (pintype "passive"))
    )
    (net (code "55") (name "Net-(JP54-Pad1)") (class "Default")
      (node (ref "JP54") (pin "1") (pinfunction "1_1") (pintype "passive"))
      (node (ref "JP54") (pin "2") (pinfunction "2_2") (pintype "passive"))
      (node (ref "JP54") (pin "3") (pinfunction "3_3") (pintype "passive"))
      (node (ref "JP54") (pin "4") (pinfunction "4_4") (pintype "passive"))
    )
    (net (code "56") (name "Net-(JP55-Pad1)") (class "Default")
      (node (ref "JP55") (pin "1") (pinfunction "1_1") (pintype "passive"))
      (node (ref "JP55") (pin "2") (pinfunction "2_2") (pintype "passive"))
      (node (ref "JP55") (pin "3") (pinfunction "3_3") (pintype "passive"))
      (node (ref "JP55") (pin "4") (pinfunction "4_4") (pintype "passive"))
    )
    (net (code "57") (name "Net-(JP56-Pad1)") (class "Default")
      (node (ref "JP56") (pin "1") (pinfunction "1_1") (pintype "passive"))
      (node (ref "JP56") (pin "2") (pinfunction "2_2") (pintype "passive"))
      (node (ref "JP56") (pin "3") (pinfunction "3_3") (pintype "passive"))
      (node (ref "JP56") (pin "4") (pinfunction "4_4") (pintype "passive"))
    )
    (net (code "58") (name "Net-(JP57-Pad1)") (class "Default")
      (node (ref "JP57") (pin "1") (pinfunction "1_1") (pintype "passive"))
      (node (ref "JP57") (pin "2") (pinfunction "2_2") (pintype "passive"))
      (node (ref "JP57") (pin "3") (pinfunction "3_3") (pintype "passive"))
      (node (ref "JP57") (pin "4") (pinfunction "4_4") (pintype "passive"))
    )
    (net (code "59") (name "Net-(JP58-Pad1)") (class "Default")
      (node (ref "JP58") (pin "1") (pinfunction "1_1") (pintype "passive"))
      (node (ref "JP58") (pin "2") (pinfunction "2_2") (pintype "passive"))
      (node (ref "JP58") (pin "3") (pinfunction "3_3") (pintype "passive"))
      (node (ref "JP58") (pin "4") (pinfunction "4_4") (pintype "passive"))
    )
    (net (code "60") (name "Net-(JP59-Pad1)") (class "Default")
      (node (ref "JP59") (pin "1") (pinfunction "1_1") (pintype "passive"))
      (node (ref "JP59") (pin "2") (pinfunction "2_2") (pintype "passive"))
      (node (ref "JP59") (pin "3") (pinfunction "3_3") (pintype "passive"))
      (node (ref "JP59") (pin "4") (pinfunction "4_4") (pintype "passive"))
    )
    (net (code "61") (name "Net-(JP60-Pad1)") (class "Default")
      (node (ref "JP60") (pin "1") (pinfunction "1_1") (pintype "passive"))
      (node (ref "JP60") (pin "2") (pinfunction "2_2") (pintype "passive"))
      (node (ref "JP60") (pin "3") (pinfunction "3_3") (pintype "passive"))
      (node (ref "JP60") (pin "4") (pinfunction "4_4") (pintype "passive"))
    )
    (net (code "62") (name "Net-(JP61-Pad1)") (class "Default")
      (node (ref "JP61") (pin "1") (pinfunction "1_1") (pintype "passive"))
      (node (ref "JP61") (pin "2") (pinfunction "2_2") (pintype "passive"))
      (node (ref "JP61") (pin "3") (pinfunction "3_3") (pintype "passive"))
      (node (ref "JP61") (pin "4") (pinfunction "4_4") (pintype "passive"))
    )
    (net (code "63") (name "Net-(JP62-Pad1)") (class "Default")
      (node (ref "JP62") (pin "1") (pinfunction "1_1") (pintype "passive"))
      (node (ref "JP62") (pin "2") (pinfunction "2_2") (pintype "passive"))
      (node (ref "JP62") (pin "3") (pinfunction "3_3") (pintype "passive"))
      (node (ref "JP62") (pin "4") (pinfunction "4_4") (pintype "passive"))
    )
    (net (code "64") (name "Net-(JP63-Pad1)") (class "Default")
      (node (ref "JP63") (pin "1") (pinfunction "1_1") (pintype "passive"))
      (node (ref "JP63") (pin "2") (pinfunction "2_2") (pintype "passive"))
      (node (ref "JP63") (pin "3") (pinfunction "3_3") (pintype "passive"))
      (node (ref "JP63") (pin "4") (pinfunction "4_4") (pintype "passive"))
    )
    (net (code "65") (name "Net-(JP64-Pad1)") (class "Default")
      (node (ref "JP64") (pin "1") (pinfunction "1_1") (pintype "passive"))
      (node (ref "JP64") (pin "2") (pinfunction "2_2") (pintype "passive"))
      (node (ref "JP64") (pin "3") (pinfunction "3_3") (pintype "passive"))
      (node (ref "JP64") (pin "4") (pinfunction "4_4") (pintype "passive"))
    )
    (net (code "66") (name "Net-(JP65-Pad1)") (class "Default")
      (node (ref "JP65") (pin "1") (pinfunction "1_1") (pintype "passive"))
      (node (ref "JP65") (pin "2") (pinfunction "2_2") (pintype "passive"))
      (node (ref "JP65") (pin "3") (pinfunction "3_3") (pintype "passive"))
      (node (ref "JP65") (pin "4") (pinfunction "4_4") (pintype "passive"))
    )
    (net (code "67") (name "Net-(JP66-Pad1)") (class "Default")
      (node (ref "JP66") (pin "1") (pinfunction "1_1") (pintype "passive"))
      (node (ref "JP66") (pin "2") (pinfunction "2_2") (pintype "passive"))
      (node (ref "JP66") (pin "3") (pinfunction "3_3") (pintype "passive"))
      (node (ref "JP66") (pin "4") (pinfunction "4_4") (pintype "passive"))
    )
    (net (code "68") (name "Net-(JP67-Pad1)") (class "Default")
      (node (ref "JP67") (pin "1") (pinfunction "1_1") (pintype "passive"))
      (node (ref "JP67") (pin "2") (pinfunction "2_2") (pintype "passive"))
      (node (ref "JP67") (pin "3") (pinfunction "3_3") (pintype "passive"))
      (node (ref "JP67") (pin "4") (pinfunction "4_4") (pintype "passive"))
    )
    (net (code "69") (name "Net-(JP68-Pad1)") (class "Default")
      (node (ref "JP68") (pin "1") (pinfunction "1_1") (pintype "passive"))
      (node (ref "JP68") (pin "2") (pinfunction "2_2") (pintype "passive"))
      (node (ref "JP68") (pin "3") (pinfunction "3_3") (pintype "passive"))
      (node (ref "JP68") (pin "4") (pinfunction "4_4") (pintype "passive"))
    )
    (net (code "70") (name "Net-(JP69-Pad1)") (class "Default")
      (node (ref "JP69") (pin "1") (pinfunction "1_1") (pintype "passive"))
      (node (ref "JP69") (pin "2") (pinfunction "2_2") (pintype "passive"))
      (node (ref "JP69") (pin "3") (pinfunction "3_3") (pintype "passive"))
      (node (ref "JP69") (pin "4") (pinfunction "4_4") (pintype "passive"))
    )
    (net (code "71") (name "Net-(JP70-Pad1)") (class "Default")
      (node (ref "JP70") (pin "1") (pinfunction "1_1") (pintype "passive"))
      (node (ref "JP70") (pin "2") (pinfunction "2_2") (pintype "passive"))
      (node (ref "JP70") (pin "3") (pinfunction "3_3") (pintype "passive"))
      (node (ref "JP70") (pin "4") (pinfunction "4_4") (pintype "passive"))
    )
    (net (code "72") (name "Net-(JP71-Pad1)") (class "Default")
      (node (ref "JP71") (pin "1") (pinfunction "1_1") (pintype "passive"))
      (node (ref "JP71") (pin "2") (pinfunction "2_2") (pintype "passive"))
      (node (ref "JP71") (pin "3") (pinfunction "3_3") (pintype "passive"))
      (node (ref "JP71") (pin "4") (pinfunction "4_4") (pintype "passive"))
    )
    (net (code "73") (name "Net-(JP72-Pad1)") (class "Default")
      (node (ref "JP72") (pin "1") (pinfunction "1_1") (pintype "passive"))
      (node (ref "JP72") (pin "2") (pinfunction "2_2") (pintype "passive"))
      (node (ref "JP72") (pin "3") (pinfunction "3_3") (pintype "passive"))
      (node (ref "JP72") (pin "4") (pinfunction "4_4") (pintype "passive"))
    )
    (net (code "74") (name "Net-(X-P)") (class "Default")
      (node (ref "X") (pin "1") (pinfunction "P_1") (pintype "passive"))
      (node (ref "X-V+") (pin "1") (pinfunction "1_1") (pintype "passive"))
      (node (ref "X-VIN") (pin "1") (pinfunction "1_1") (pintype "passive"))
    )
    (net (code "75") (name "Net-(Y-P)") (class "Default")
      (node (ref "Y") (pin "1") (pinfunction "P_1") (pintype "passive"))
      (node (ref "Y-GND") (pin "1") (pinfunction "1_1") (pintype "passive"))
      (node (ref "Y-V-") (pin "1") (pinfunction "1_1") (pintype "passive"))
    )
    (net (code "76") (name "V+") (class "Default")
      (node (ref "B-V+") (pin "1") (pinfunction "1_1") (pintype "passive"))
      (node (ref "C-V+") (pin "1") (pinfunction "1_1") (pintype "passive"))
      (node (ref "X-V+") (pin "2") (pinfunction "2_2") (pintype "passive"))
    )
    (net (code "77") (name "V-") (class "Default")
      (node (ref "B-V-") (pin "1") (pinfunction "1_1") (pintype "passive"))
      (node (ref "C-V-") (pin "1") (pinfunction "1_1") (pintype "passive"))
      (node (ref "Y-V-") (pin "2") (pinfunction "2_2") (pintype "passive"))
    )
    (net (code "78") (name "VIN") (class "Default")
      (node (ref "JP22") (pin "1") (pinfunction "1_1") (pintype "passive"))
      (node (ref "JP22") (pin "2") (pinfunction "2_2") (pintype "passive"))
      (node (ref "JP22") (pin "3") (pinfunction "3_3") (pintype "passive"))
      (node (ref "POWER") (pin "8") (pinfunction "8_8") (pintype "passive"))
      (node (ref "X-VIN") (pin "2") (pinfunction "2_2") (pintype "passive"))
    )
  )
)
